# rz568m-test-v1.net
KiCad netlist of a schematic drawn in EAGLE
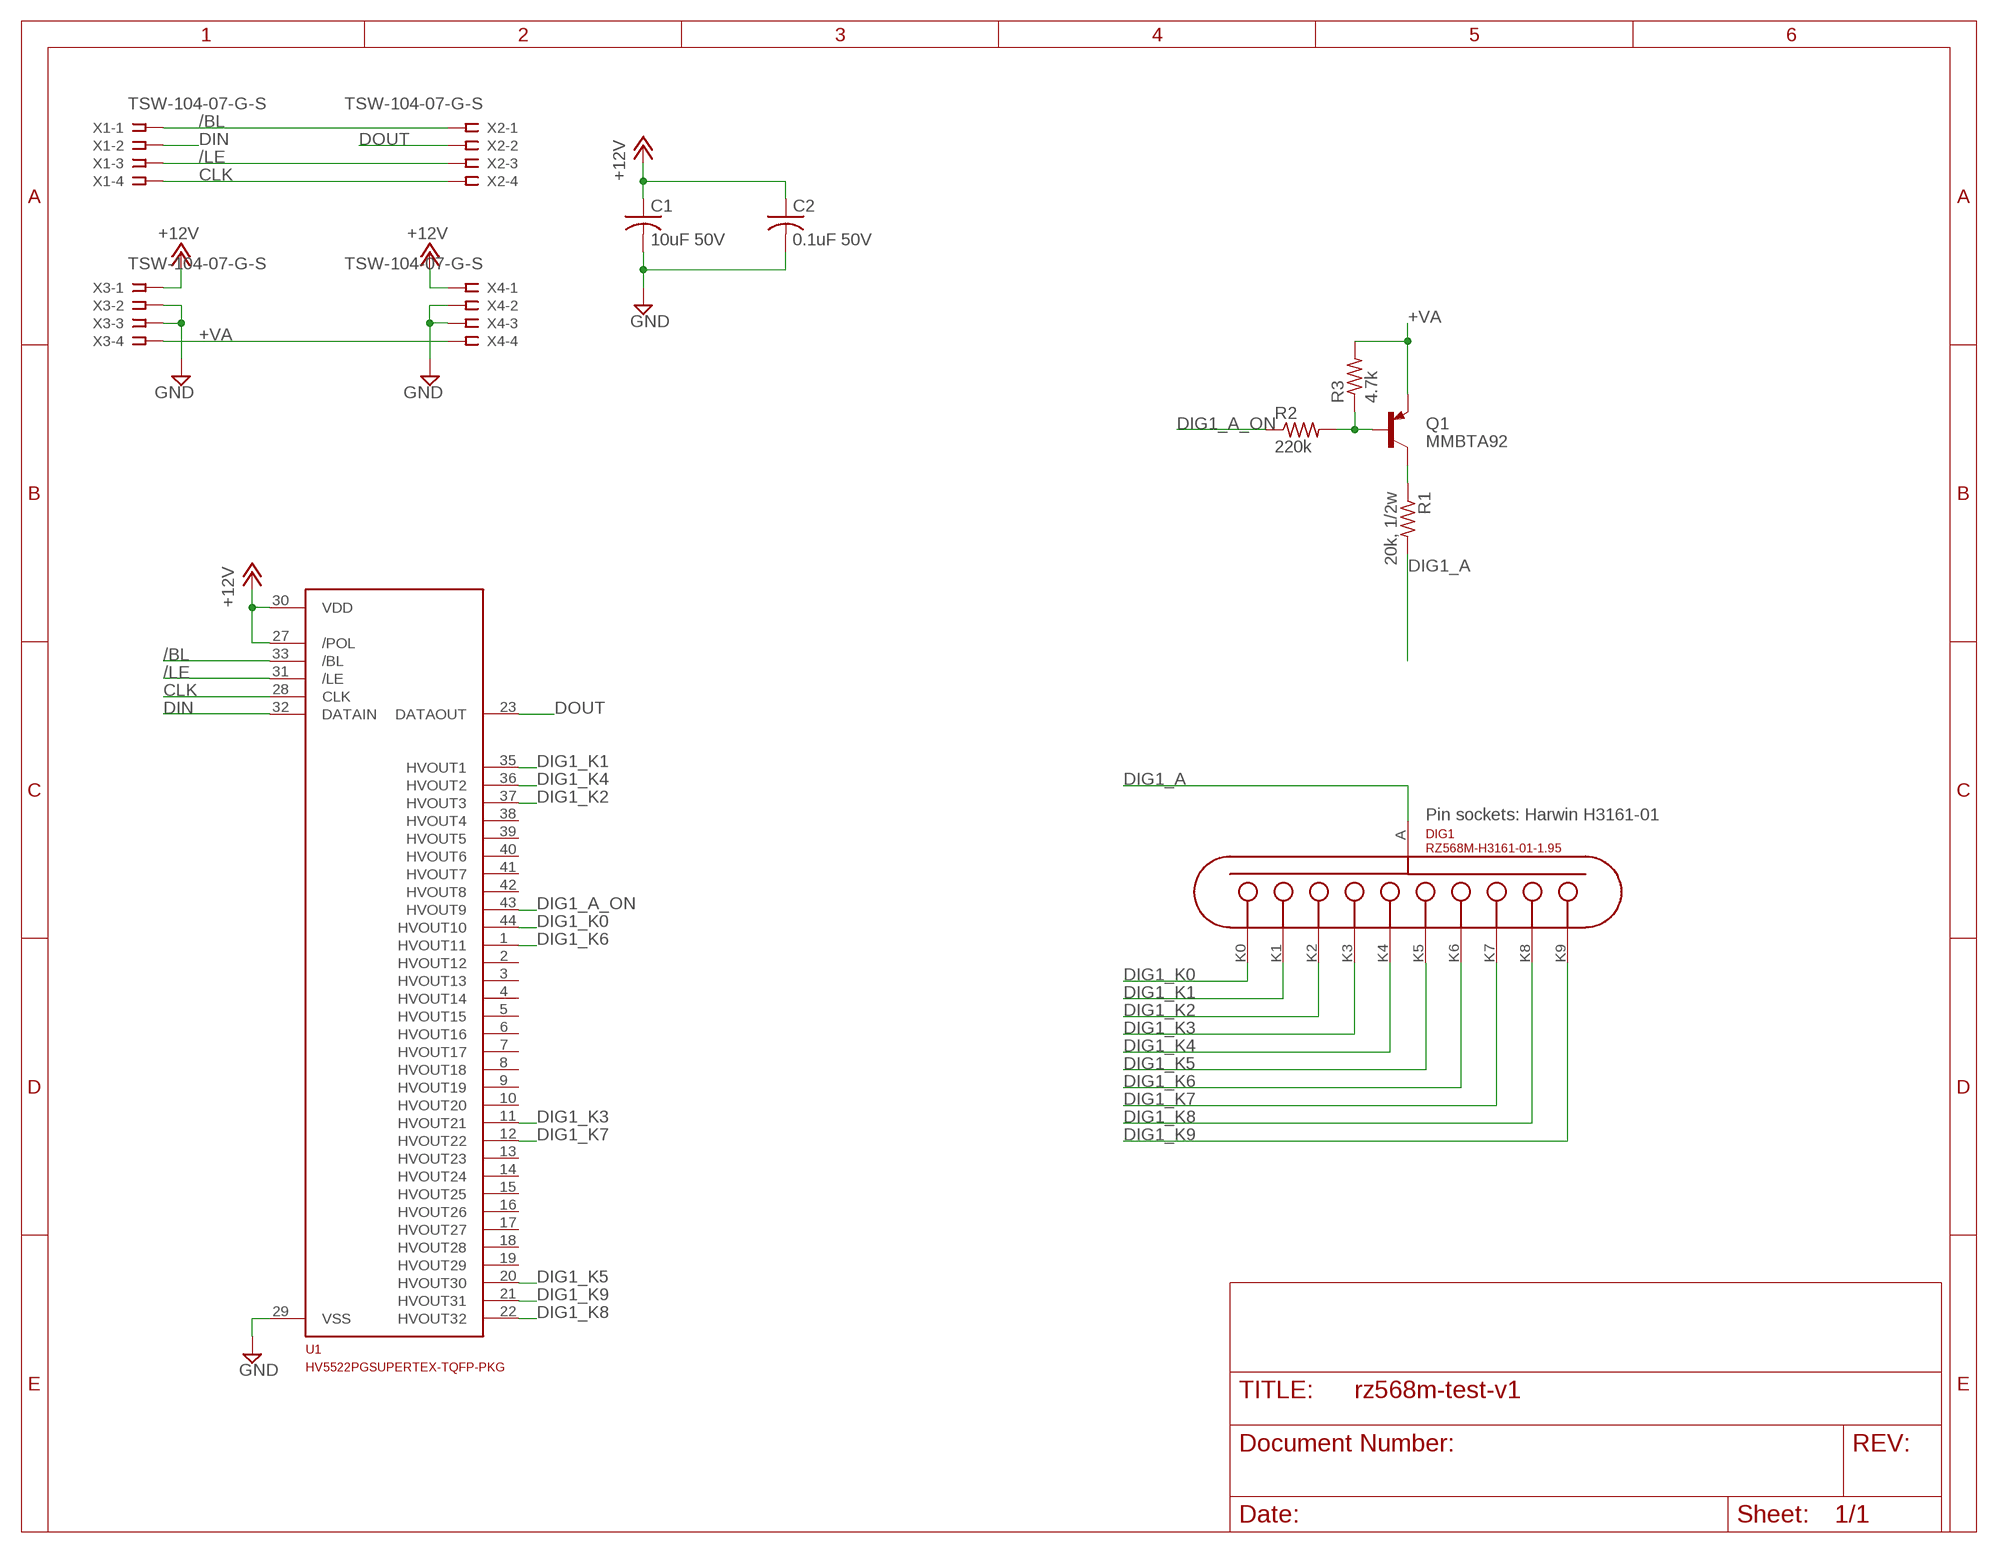
[diagram p0: schematic, sheet 1]

(export (version "E")
  (design (tool "Eeschema 10.0.6"))
  (components
    (comp (ref "C1")
      (value "10uF 50V")
      (footprint "eagle-import:C1210K")
      (fields (field (name "MFR") "KEMET") (field (name "MFR_PART_NO") "C1210C106K5RACTU"))
      (libsource (lib "eagle-import") (part "C-USC1210K"))
    )
    (comp (ref "C2")
      (value "0.1uF 50V")
      (footprint "eagle-import:C1206K")
      (fields (field (name "MFR") "KEMET") (field (name "MFR_PART_NO") "C1206S104M5RACTU"))
      (libsource (lib "eagle-import") (part "C-USC1206K"))
    )
    (comp (ref "DIG1")
      (value "RZ568M-H3161-01-1.95")
      (footprint "eagle-import:RZ568M-H3161-01-1.95")
      (fields (field (name "MFR") "HARWIN") (field (name "MFR_PART_NO") "H3161-01"))
      (libsource (lib "eagle-import") (part "RZ568M-H3161-01-1.95"))
    )
    (comp (ref "Q1")
      (value "MMBTA92")
      (footprint "eagle-import:SOT23-BEC")
      (fields (field (name "MFR") "ON SEMI"))
      (libsource (lib "eagle-import") (part "-PNP-SOT23-BECMMBTA92LT1"))
    )
    (comp (ref "R1")
      (value "20k, 1/2w")
      (footprint "eagle-import:R1210")
      (fields (field (name "MFR") "PANASONIC") (field (name "MFR_PART_NO") "ERJ-14NF2002U"))
      (libsource (lib "eagle-import") (part "R-US_R1210"))
    )
    (comp (ref "R2")
      (value "220k")
      (footprint "eagle-import:R1206")
      (fields (field (name "MFR") "PANASONIC") (field (name "MFR_PART_NO") "ERJ-8GEYJ224V"))
      (libsource (lib "eagle-import") (part "R-US_R1206"))
    )
    (comp (ref "R3")
      (value "4.7k")
      (footprint "eagle-import:R1206")
      (fields (field (name "MFR") "PANASONIC") (field (name "MFR_PART_NO") "ERJ-8ENF4701V"))
      (libsource (lib "eagle-import") (part "R-US_R1206"))
    )
    (comp (ref "U1")
      (value "HV5522PGSUPERTEX-TQFP-PKG")
      (footprint "eagle-import:TQFP44-HV5522PG")
      (fields (field (name "MFR") "MICROCHIP") (field (name "MFR_PART_NO") "HV5522PG"))
      (libsource (lib "eagle-import") (part "HV5522PGSUPERTEX-TQFP-PKG"))
    )
    (comp (ref "X1")
      (value "TSW-104-07-G-S")
      (footprint "eagle-import:SSW-104-02-S-S")
      (fields
        (field (name "MPN") "SSW-104-02-S-S")
        (field (name "MFR") "SAMTEC")
        (field (name "MFR_PART_NO") "TSW-104-07-G-S")
      )
      (libsource (lib "eagle-import") (part "SSW-104-02-S-S"))
    )
    (comp (ref "X2")
      (value "TSW-104-07-G-S")
      (footprint "eagle-import:SSW-104-02-S-S")
      (fields
        (field (name "MPN") "SSW-104-02-S-S")
        (field (name "MFR") "SAMTEC")
        (field (name "MFR_PART_NO") "TSW-104-07-G-S")
      )
      (libsource (lib "eagle-import") (part "SSW-104-02-S-S"))
    )
    (comp (ref "X3")
      (value "TSW-104-07-G-S")
      (footprint "eagle-import:SSW-104-02-S-S")
      (fields
        (field (name "MPN") "SSW-104-02-S-S")
        (field (name "MFR") "SAMTEC")
        (field (name "MFR_PART_NO") "TSW-104-07-G-S")
      )
      (libsource (lib "eagle-import") (part "SSW-104-02-S-S"))
    )
    (comp (ref "X4")
      (value "TSW-104-07-G-S")
      (footprint "eagle-import:SSW-104-02-S-S")
      (fields
        (field (name "MPN") "SSW-104-02-S-S")
        (field (name "MFR") "SAMTEC")
        (field (name "MFR_PART_NO") "TSW-104-07-G-S")
      )
      (libsource (lib "eagle-import") (part "SSW-104-02-S-S"))
    )
  )
  (nets
    (net (code "1") (name "+12V") (class "Default")
      (node (ref "C1") (pin "1") (pinfunction "1_1") (pintype "passive"))
      (node (ref "C2") (pin "1") (pinfunction "1_1") (pintype "passive"))
      (node (ref "U1") (pin "27") (pinfunction "/POL_27") (pintype "bidirectional"))
      (node (ref "U1") (pin "30") (pinfunction "VDD_30") (pintype "bidirectional"))
      (node (ref "X3") (pin "1") (pinfunction "1_1") (pintype "passive"))
      (node (ref "X4") (pin "1") (pinfunction "1_1") (pintype "passive"))
    )
    (net (code "2") (name "/+VA") (class "Default")
      (node (ref "Q1") (pin "E") (pinfunction "E_E") (pintype "passive"))
      (node (ref "R3") (pin "2") (pinfunction "2_2") (pintype "passive"))
      (node (ref "X3") (pin "4") (pinfunction "1_4") (pintype "passive"))
      (node (ref "X4") (pin "4") (pinfunction "1_4") (pintype "passive"))
    )
    (net (code "3") (name "/CLK") (class "Default")
      (node (ref "U1") (pin "28") (pinfunction "CLK_28") (pintype "bidirectional"))
      (node (ref "X1") (pin "4") (pinfunction "1_4") (pintype "passive"))
      (node (ref "X2") (pin "4") (pinfunction "1_4") (pintype "passive"))
    )
    (net (code "4") (name "/DIG1_A") (class "Default")
      (node (ref "DIG1") (pin "A") (pinfunction "A_A") (pintype "bidirectional"))
      (node (ref "R1") (pin "2") (pinfunction "2_2") (pintype "passive"))
    )
    (net (code "5") (name "/DIG1_A_ON") (class "Default")
      (node (ref "R2") (pin "1") (pinfunction "1_1") (pintype "passive"))
      (node (ref "U1") (pin "43") (pinfunction "HVOUT9_43") (pintype "bidirectional"))
    )
    (net (code "6") (name "/DIG1_K0") (class "Default")
      (node (ref "DIG1") (pin "K0") (pinfunction "K0_K0") (pintype "bidirectional"))
      (node (ref "U1") (pin "44") (pinfunction "HVOUT10_44") (pintype "bidirectional"))
    )
    (net (code "7") (name "/DIG1_K1") (class "Default")
      (node (ref "DIG1") (pin "K1") (pinfunction "K1_K1") (pintype "bidirectional"))
      (node (ref "U1") (pin "35") (pinfunction "HVOUT1_35") (pintype "bidirectional"))
    )
    (net (code "8") (name "/DIG1_K2") (class "Default")
      (node (ref "DIG1") (pin "K2") (pinfunction "K2_K2") (pintype "bidirectional"))
      (node (ref "U1") (pin "37") (pinfunction "HVOUT3_37") (pintype "bidirectional"))
    )
    (net (code "9") (name "/DIG1_K3") (class "Default")
      (node (ref "DIG1") (pin "K3") (pinfunction "K3_K3") (pintype "bidirectional"))
      (node (ref "U1") (pin "11") (pinfunction "HVOUT21_11") (pintype "bidirectional"))
    )
    (net (code "10") (name "/DIG1_K4") (class "Default")
      (node (ref "DIG1") (pin "K4") (pinfunction "K4_K4") (pintype "bidirectional"))
      (node (ref "U1") (pin "36") (pinfunction "HVOUT2_36") (pintype "bidirectional"))
    )
    (net (code "11") (name "/DIG1_K5") (class "Default")
      (node (ref "DIG1") (pin "K5") (pinfunction "K5_K5") (pintype "bidirectional"))
      (node (ref "U1") (pin "20") (pinfunction "HVOUT30_20") (pintype "bidirectional"))
    )
    (net (code "12") (name "/DIG1_K6") (class "Default")
      (node (ref "DIG1") (pin "K6") (pinfunction "K6_K6") (pintype "bidirectional"))
      (node (ref "U1") (pin "1") (pinfunction "HVOUT11_1") (pintype "bidirectional"))
    )
    (net (code "13") (name "/DIG1_K7") (class "Default")
      (node (ref "DIG1") (pin "K7") (pinfunction "K7_K7") (pintype "bidirectional"))
      (node (ref "U1") (pin "12") (pinfunction "HVOUT22_12") (pintype "bidirectional"))
    )
    (net (code "14") (name "/DIG1_K8") (class "Default")
      (node (ref "DIG1") (pin "K8") (pinfunction "K8_K8") (pintype "bidirectional"))
      (node (ref "U1") (pin "22") (pinfunction "HVOUT32_22") (pintype "bidirectional"))
    )
    (net (code "15") (name "/DIG1_K9") (class "Default")
      (node (ref "DIG1") (pin "K9") (pinfunction "K9_K9") (pintype "bidirectional"))
      (node (ref "U1") (pin "21") (pinfunction "HVOUT31_21") (pintype "bidirectional"))
    )
    (net (code "16") (name "/DIN") (class "Default")
      (node (ref "U1") (pin "32") (pinfunction "DATAIN_32") (pintype "bidirectional"))
      (node (ref "X1") (pin "2") (pinfunction "1_2") (pintype "passive"))
    )
    (net (code "17") (name "/DOUT") (class "Default")
      (node (ref "U1") (pin "23") (pinfunction "DATAOUT_23") (pintype "bidirectional"))
      (node (ref "X2") (pin "2") (pinfunction "1_2") (pintype "passive"))
    )
    (net (code "18") (name "/{slash}BL") (class "Default")
      (node (ref "U1") (pin "33") (pinfunction "/BL_33") (pintype "bidirectional"))
      (node (ref "X1") (pin "1") (pinfunction "1_1") (pintype "passive"))
      (node (ref "X2") (pin "1") (pinfunction "1_1") (pintype "passive"))
    )
    (net (code "19") (name "/{slash}LE") (class "Default")
      (node (ref "U1") (pin "31") (pinfunction "/LE_31") (pintype "bidirectional"))
      (node (ref "X1") (pin "3") (pinfunction "1_3") (pintype "passive"))
      (node (ref "X2") (pin "3") (pinfunction "1_3") (pintype "passive"))
    )
    (net (code "20") (name "GND") (class "Default")
      (node (ref "C1") (pin "2") (pinfunction "2_2") (pintype "passive"))
      (node (ref "C2") (pin "2") (pinfunction "2_2") (pintype "passive"))
      (node (ref "U1") (pin "29") (pinfunction "VSS_29") (pintype "bidirectional"))
      (node (ref "X3") (pin "2") (pinfunction "1_2") (pintype "passive"))
      (node (ref "X3") (pin "3") (pinfunction "1_3") (pintype "passive"))
      (node (ref "X4") (pin "2") (pinfunction "1_2") (pintype "passive"))
      (node (ref "X4") (pin "3") (pinfunction "1_3") (pintype "passive"))
    )
    (net (code "21") (name "Net-(Q1-PadB)") (class "Default")
      (node (ref "Q1") (pin "B") (pinfunction "B_B") (pintype "passive"))
      (node (ref "R2") (pin "2") (pinfunction "2_2") (pintype "passive"))
      (node (ref "R3") (pin "1") (pinfunction "1_1") (pintype "passive"))
    )
    (net (code "22") (name "Net-(Q1-PadC)") (class "Default")
      (node (ref "Q1") (pin "C") (pinfunction "C_C") (pintype "passive"))
      (node (ref "R1") (pin "1") (pinfunction "1_1") (pintype "passive"))
    )
    (net (code "23") (name "unconnected-(U1-HVOUT4-Pad38)") (class "Default")
      (node (ref "U1") (pin "38") (pinfunction "HVOUT4_38") (pintype "bidirectional"))
    )
    (net (code "24") (name "unconnected-(U1-HVOUT5-Pad39)") (class "Default")
      (node (ref "U1") (pin "39") (pinfunction "HVOUT5_39") (pintype "bidirectional"))
    )
    (net (code "25") (name "unconnected-(U1-HVOUT6-Pad40)") (class "Default")
      (node (ref "U1") (pin "40") (pinfunction "HVOUT6_40") (pintype "bidirectional"))
    )
    (net (code "26") (name "unconnected-(U1-HVOUT7-Pad41)") (class "Default")
      (node (ref "U1") (pin "41") (pinfunction "HVOUT7_41") (pintype "bidirectional"))
    )
    (net (code "27") (name "unconnected-(U1-HVOUT8-Pad42)") (class "Default")
      (node (ref "U1") (pin "42") (pinfunction "HVOUT8_42") (pintype "bidirectional"))
    )
    (net (code "28") (name "unconnected-(U1-HVOUT12-Pad2)") (class "Default")
      (node (ref "U1") (pin "2") (pinfunction "HVOUT12_2") (pintype "bidirectional"))
    )
    (net (code "29") (name "unconnected-(U1-HVOUT13-Pad3)") (class "Default")
      (node (ref "U1") (pin "3") (pinfunction "HVOUT13_3") (pintype "bidirectional"))
    )
    (net (code "30") (name "unconnected-(U1-HVOUT14-Pad4)") (class "Default")
      (node (ref "U1") (pin "4") (pinfunction "HVOUT14_4") (pintype "bidirectional"))
    )
    (net (code "31") (name "unconnected-(U1-HVOUT15-Pad5)") (class "Default")
      (node (ref "U1") (pin "5") (pinfunction "HVOUT15_5") (pintype "bidirectional"))
    )
    (net (code "32") (name "unconnected-(U1-HVOUT16-Pad6)") (class "Default")
      (node (ref "U1") (pin "6") (pinfunction "HVOUT16_6") (pintype "bidirectional"))
    )
    (net (code "33") (name "unconnected-(U1-HVOUT17-Pad7)") (class "Default")
      (node (ref "U1") (pin "7") (pinfunction "HVOUT17_7") (pintype "bidirectional"))
    )
    (net (code "34") (name "unconnected-(U1-HVOUT18-Pad8)") (class "Default")
      (node (ref "U1") (pin "8") (pinfunction "HVOUT18_8") (pintype "bidirectional"))
    )
    (net (code "35") (name "unconnected-(U1-HVOUT19-Pad9)") (class "Default")
      (node (ref "U1") (pin "9") (pinfunction "HVOUT19_9") (pintype "bidirectional"))
    )
    (net (code "36") (name "unconnected-(U1-HVOUT20-Pad10)") (class "Default")
      (node (ref "U1") (pin "10") (pinfunction "HVOUT20_10") (pintype "bidirectional"))
    )
    (net (code "37") (name "unconnected-(U1-HVOUT23-Pad13)") (class "Default")
      (node (ref "U1") (pin "13") (pinfunction "HVOUT23_13") (pintype "bidirectional"))
    )
    (net (code "38") (name "unconnected-(U1-HVOUT24-Pad14)") (class "Default")
      (node (ref "U1") (pin "14") (pinfunction "HVOUT24_14") (pintype "bidirectional"))
    )
    (net (code "39") (name "unconnected-(U1-HVOUT25-Pad15)") (class "Default")
      (node (ref "U1") (pin "15") (pinfunction "HVOUT25_15") (pintype "bidirectional"))
    )
    (net (code "40") (name "unconnected-(U1-HVOUT26-Pad16)") (class "Default")
      (node (ref "U1") (pin "16") (pinfunction "HVOUT26_16") (pintype "bidirectional"))
    )
    (net (code "41") (name "unconnected-(U1-HVOUT27-Pad17)") (class "Default")
      (node (ref "U1") (pin "17") (pinfunction "HVOUT27_17") (pintype "bidirectional"))
    )
    (net (code "42") (name "unconnected-(U1-HVOUT28-Pad18)") (class "Default")
      (node (ref "U1") (pin "18") (pinfunction "HVOUT28_18") (pintype "bidirectional"))
    )
    (net (code "43") (name "unconnected-(U1-HVOUT29-Pad19)") (class "Default")
      (node (ref "U1") (pin "19") (pinfunction "HVOUT29_19") (pintype "bidirectional"))
    )
  )
)
